# schematic.net
KiCad netlist of a schematic drawn in Altium Designer
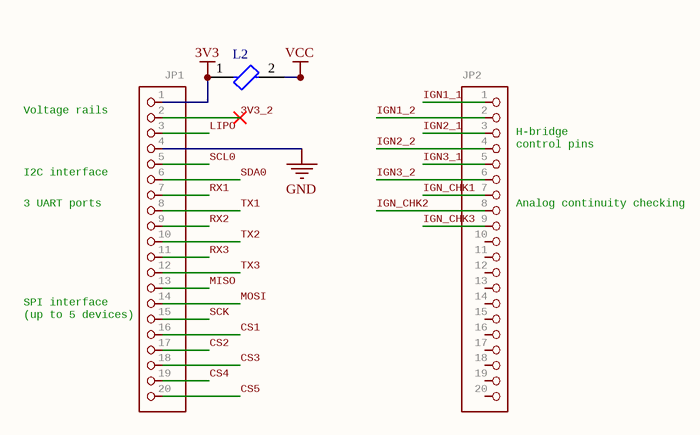
[diagram p0: schematic.SchDoc]

(export (version "E")
  (design (tool "Eeschema 10.0.6"))
  (components
    (comp (ref "JP1")
      (value "PINHD-1X20")
      (footprint "1X20")
      (description "PIN HEADER")
      (libsource (lib "adafruit") (part "PINHD-1X20"))
    )
    (comp (ref "JP2")
      (value "PINHD-1X20")
      (footprint "1X20")
      (description "PIN HEADER")
      (libsource (lib "adafruit") (part "PINHD-1X20"))
    )
    (comp (ref "L2")
      (value "BLM18EG601SN1D")
      (footprint "FP-BLM18-0_15-t0_8-MFG")
      (description "Chip Ferrite Bead, 0603, 600Ω @ 100MHz, 0.35Ω, 25%, 500mA")
      (fields (field (name "TOLERANCE") "25%") (field (name "LCSC PART #") "C20345"))
      (libsource (lib "Altium Content Vault") (part "5f30dd21d616792df468990f7003faa"))
    )
  )
  (nets
    (net (code "1") (name "/3V3_2") (class "Default")
      (node (ref "JP1") (pin "2") (pinfunction "2_2") (pintype "passive+no_connect"))
    )
    (net (code "2") (name "/CS1") (class "Default")
      (node (ref "JP1") (pin "16") (pinfunction "16_16") (pintype "passive"))
    )
    (net (code "3") (name "/CS2") (class "Default")
      (node (ref "JP1") (pin "17") (pinfunction "17_17") (pintype "passive"))
    )
    (net (code "4") (name "/CS3") (class "Default")
      (node (ref "JP1") (pin "18") (pinfunction "18_18") (pintype "passive"))
    )
    (net (code "5") (name "/CS4") (class "Default")
      (node (ref "JP1") (pin "19") (pinfunction "19_19") (pintype "passive"))
    )
    (net (code "6") (name "/CS5") (class "Default")
      (node (ref "JP1") (pin "20") (pinfunction "20_20") (pintype "passive"))
    )
    (net (code "7") (name "/IGN1_1") (class "Default")
      (node (ref "JP2") (pin "1") (pinfunction "1_1") (pintype "passive"))
    )
    (net (code "8") (name "/IGN1_2") (class "Default")
      (node (ref "JP2") (pin "2") (pinfunction "2_2") (pintype "passive"))
    )
    (net (code "9") (name "/IGN2_1") (class "Default")
      (node (ref "JP2") (pin "3") (pinfunction "3_3") (pintype "passive"))
    )
    (net (code "10") (name "/IGN2_2") (class "Default")
      (node (ref "JP2") (pin "4") (pinfunction "4_4") (pintype "passive"))
    )
    (net (code "11") (name "/IGN3_1") (class "Default")
      (node (ref "JP2") (pin "5") (pinfunction "5_5") (pintype "passive"))
    )
    (net (code "12") (name "/IGN3_2") (class "Default")
      (node (ref "JP2") (pin "6") (pinfunction "6_6") (pintype "passive"))
    )
    (net (code "13") (name "/IGN_CHK1") (class "Default")
      (node (ref "JP2") (pin "7") (pinfunction "7_7") (pintype "passive"))
    )
    (net (code "14") (name "/IGN_CHK2") (class "Default")
      (node (ref "JP2") (pin "8") (pinfunction "8_8") (pintype "passive"))
    )
    (net (code "15") (name "/IGN_CHK3") (class "Default")
      (node (ref "JP2") (pin "9") (pinfunction "9_9") (pintype "passive"))
    )
    (net (code "16") (name "/LIPO") (class "Default")
      (node (ref "JP1") (pin "3") (pinfunction "3_3") (pintype "passive"))
    )
    (net (code "17") (name "/MISO") (class "Default")
      (node (ref "JP1") (pin "13") (pinfunction "13_13") (pintype "passive"))
    )
    (net (code "18") (name "/MOSI") (class "Default")
      (node (ref "JP1") (pin "14") (pinfunction "14_14") (pintype "passive"))
    )
    (net (code "19") (name "/RX1") (class "Default")
      (node (ref "JP1") (pin "7") (pinfunction "7_7") (pintype "passive"))
    )
    (net (code "20") (name "/RX2") (class "Default")
      (node (ref "JP1") (pin "9") (pinfunction "9_9") (pintype "passive"))
    )
    (net (code "21") (name "/RX3") (class "Default")
      (node (ref "JP1") (pin "11") (pinfunction "11_11") (pintype "passive"))
    )
    (net (code "22") (name "/SCK") (class "Default")
      (node (ref "JP1") (pin "15") (pinfunction "15_15") (pintype "passive"))
    )
    (net (code "23") (name "/SCL0") (class "Default")
      (node (ref "JP1") (pin "5") (pinfunction "5_5") (pintype "passive"))
    )
    (net (code "24") (name "/SDA0") (class "Default")
      (node (ref "JP1") (pin "6") (pinfunction "6_6") (pintype "passive"))
    )
    (net (code "25") (name "/TX1") (class "Default")
      (node (ref "JP1") (pin "8") (pinfunction "8_8") (pintype "passive"))
    )
    (net (code "26") (name "/TX2") (class "Default")
      (node (ref "JP1") (pin "10") (pinfunction "10_10") (pintype "passive"))
    )
    (net (code "27") (name "/TX3") (class "Default")
      (node (ref "JP1") (pin "12") (pinfunction "12_12") (pintype "passive"))
    )
    (net (code "28") (name "3V3") (class "Default")
      (node (ref "JP1") (pin "1") (pinfunction "1_1") (pintype "passive"))
      (node (ref "L2") (pin "1") (pinfunction "1_1") (pintype "passive"))
    )
    (net (code "29") (name "GND") (class "Default")
      (node (ref "JP1") (pin "4") (pinfunction "4_4") (pintype "passive"))
    )
    (net (code "30") (name "VCC") (class "Default")
      (node (ref "L2") (pin "2") (pinfunction "2_2") (pintype "passive"))
    )
    (net (code "31") (name "unconnected-(JP2-Pad10)") (class "Default")
      (node (ref "JP2") (pin "10") (pinfunction "10_10") (pintype "passive"))
    )
    (net (code "32") (name "unconnected-(JP2-Pad11)") (class "Default")
      (node (ref "JP2") (pin "11") (pinfunction "11_11") (pintype "passive"))
    )
    (net (code "33") (name "unconnected-(JP2-Pad12)") (class "Default")
      (node (ref "JP2") (pin "12") (pinfunction "12_12") (pintype "passive"))
    )
    (net (code "34") (name "unconnected-(JP2-Pad13)") (class "Default")
      (node (ref "JP2") (pin "13") (pinfunction "13_13") (pintype "passive"))
    )
    (net (code "35") (name "unconnected-(JP2-Pad14)") (class "Default")
      (node (ref "JP2") (pin "14") (pinfunction "14_14") (pintype "passive"))
    )
    (net (code "36") (name "unconnected-(JP2-Pad15)") (class "Default")
      (node (ref "JP2") (pin "15") (pinfunction "15_15") (pintype "passive"))
    )
    (net (code "37") (name "unconnected-(JP2-Pad16)") (class "Default")
      (node (ref "JP2") (pin "16") (pinfunction "16_16") (pintype "passive"))
    )
    (net (code "38") (name "unconnected-(JP2-Pad17)") (class "Default")
      (node (ref "JP2") (pin "17") (pinfunction "17_17") (pintype "passive"))
    )
    (net (code "39") (name "unconnected-(JP2-Pad18)") (class "Default")
      (node (ref "JP2") (pin "18") (pinfunction "18_18") (pintype "passive"))
    )
    (net (code "40") (name "unconnected-(JP2-Pad19)") (class "Default")
      (node (ref "JP2") (pin "19") (pinfunction "19_19") (pintype "passive"))
    )
    (net (code "41") (name "unconnected-(JP2-Pad20)") (class "Default")
      (node (ref "JP2") (pin "20") (pinfunction "20_20") (pintype "passive"))
    )
  )
)
